# Ports.net
KiCad netlist of a schematic drawn in Altium Designer
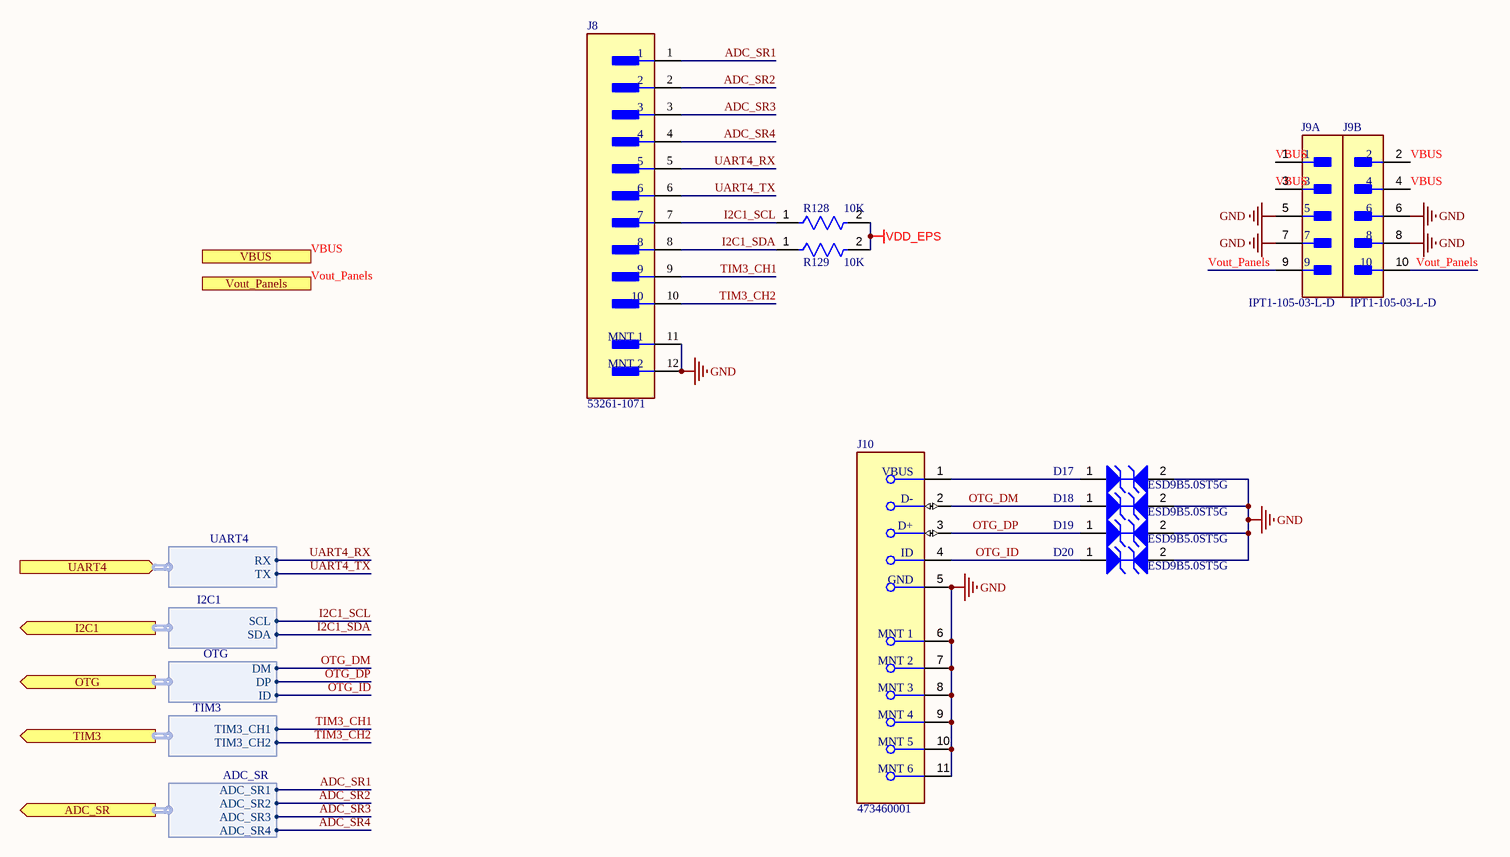
[diagram p0: Ports.SchDoc]

(export (version "E")
  (design (tool "Eeschema 10.0.6"))
  (components
    (comp (ref "D17")
      (value "ESD9B5.0ST5G")
      (footprint "ONSC-SOD-923-2-514AB-01_V")
      (fields (field (name "MANUFACTURER") "On Semiconductor"))
      (libsource (lib "Altium Content Vault") (part "ONSC-A1A2-2"))
    )
    (comp (ref "D18")
      (value "ESD9B5.0ST5G")
      (footprint "ONSC-SOD-923-2-514AB-01_V")
      (fields (field (name "MANUFACTURER") "On Semiconductor"))
      (libsource (lib "Altium Content Vault") (part "ONSC-A1A2-2"))
    )
    (comp (ref "D19")
      (value "ESD9B5.0ST5G")
      (footprint "ONSC-SOD-923-2-514AB-01_V")
      (fields (field (name "MANUFACTURER") "On Semiconductor"))
      (libsource (lib "Altium Content Vault") (part "ONSC-A1A2-2"))
    )
    (comp (ref "D20")
      (value "ESD9B5.0ST5G")
      (footprint "ONSC-SOD-923-2-514AB-01_V")
      (fields (field (name "MANUFACTURER") "On Semiconductor"))
      (libsource (lib "Altium Content Vault") (part "ONSC-A1A2-2"))
    )
    (comp (ref "J8")
      (value "53261-1071")
      (footprint "FP-532611071-MFG")
      (libsource (lib "Altium Content Vault") (part "6fa52caac0d1ee56d9e6a1d806c5b84"))
    )
    (comp (ref "J9")
      (value "IPT1-105-03-L-D")
      (footprint "FP-IPT1-105-03-L-D-MFG")
      (description "CONN HEADER VERT 10POS 2.54MM")
      (fields
        (field (name "MANUFACTURER") "Samtec")
        (field (name "OCTOPART") "https://octopart.com/ipt1-105-03-l-d-samtec-19544968")
      )
      (libsource (lib "") (part "544f42128f4185dcb88ce1ce9bf1982_1"))
    )
    (comp (ref "J10")
      (value "473460001")
      (footprint "FP-473460001-MFG")
      (description "CONN RCPT USB2.0 MICRO B SMD R/A")
      (fields
        (field (name "OCTOPART") "https://octopart.com/47346-0001-molex-7164928")
        (field (name "MANUFACTURER") "Molex")
      )
      (libsource (lib "Altium Content Vault") (part "53ae1f1d9b557310b43ca686e5bb76a"))
    )
    (comp (ref "R128")
      (value "10K")
      (footprint "FP-RK73B1J-MFG")
      (description "RES 10K OHM 5% 1/10W 0603")
      (fields (field (name "TOLERANCE") "5%"))
      (libsource (lib "Altium Content Vault") (part "1029c3af85768c4190bb7ad29bc67b5"))
    )
    (comp (ref "R129")
      (value "10K")
      (footprint "FP-RK73B1J-MFG")
      (description "RES 10K OHM 5% 1/10W 0603")
      (fields (field (name "TOLERANCE") "5%"))
      (libsource (lib "Altium Content Vault") (part "1029c3af85768c4190bb7ad29bc67b5"))
    )
  )
  (nets
    (net (code "6") (name "/ADC_SR1") (class "Default")
      (node (ref "J8") (pin "1") (pinfunction "1_1") (pintype "passive"))
    )
    (net (code "7") (name "/ADC_SR2") (class "Default")
      (node (ref "J8") (pin "2") (pinfunction "2_2") (pintype "passive"))
    )
    (net (code "8") (name "/ADC_SR3") (class "Default")
      (node (ref "J8") (pin "3") (pinfunction "3_3") (pintype "passive"))
    )
    (net (code "9") (name "/ADC_SR4") (class "Default")
      (node (ref "J8") (pin "4") (pinfunction "4_4") (pintype "passive"))
    )
    (net (code "10") (name "/I2C1_SCL") (class "Default")
      (node (ref "J8") (pin "7") (pinfunction "7_7") (pintype "passive"))
      (node (ref "R128") (pin "1") (pinfunction "1_1") (pintype "passive"))
    )
    (net (code "11") (name "/I2C1_SDA") (class "Default")
      (node (ref "J8") (pin "8") (pinfunction "8_8") (pintype "passive"))
      (node (ref "R129") (pin "1") (pinfunction "1_1") (pintype "passive"))
    )
    (net (code "12") (name "/OTG_DM") (class "Default")
      (node (ref "D18") (pin "1") (pinfunction "A1_1") (pintype "passive"))
      (node (ref "J10") (pin "2") (pinfunction "D-_2") (pintype "bidirectional"))
    )
    (net (code "13") (name "/OTG_DP") (class "Default")
      (node (ref "D19") (pin "1") (pinfunction "A1_1") (pintype "passive"))
      (node (ref "J10") (pin "3") (pinfunction "D+_3") (pintype "bidirectional"))
    )
    (net (code "14") (name "/OTG_ID") (class "Default")
      (node (ref "D20") (pin "1") (pinfunction "A1_1") (pintype "passive"))
      (node (ref "J10") (pin "4") (pinfunction "ID_4") (pintype "passive"))
    )
    (net (code "15") (name "/TIM3_CH1") (class "Default")
      (node (ref "J8") (pin "9") (pinfunction "9_9") (pintype "passive"))
    )
    (net (code "16") (name "/TIM3_CH2") (class "Default")
      (node (ref "J8") (pin "10") (pinfunction "10_10") (pintype "passive"))
    )
    (net (code "17") (name "/UART4_RX") (class "Default")
      (node (ref "J8") (pin "5") (pinfunction "5_5") (pintype "passive"))
    )
    (net (code "18") (name "/UART4_TX") (class "Default")
      (node (ref "J8") (pin "6") (pinfunction "6_6") (pintype "passive"))
    )
    (net (code "19") (name "/VBUS") (class "Default")
      (node (ref "J9") (pin "1") (pinfunction "1_1") (pintype "passive"))
      (node (ref "J9") (pin "2") (pinfunction "2_2") (pintype "passive"))
      (node (ref "J9") (pin "3") (pinfunction "3_3") (pintype "passive"))
      (node (ref "J9") (pin "4") (pinfunction "4_4") (pintype "passive"))
    )
    (net (code "20") (name "/Vout_Panels") (class "Default")
      (node (ref "J9") (pin "10") (pinfunction "10_10") (pintype "passive"))
      (node (ref "J9") (pin "9") (pinfunction "9_9") (pintype "passive"))
    )
    (net (code "26") (name "GND") (class "Default")
      (node (ref "D17") (pin "2") (pinfunction "A2_2") (pintype "passive"))
      (node (ref "D18") (pin "2") (pinfunction "A2_2") (pintype "passive"))
      (node (ref "D19") (pin "2") (pinfunction "A2_2") (pintype "passive"))
      (node (ref "D20") (pin "2") (pinfunction "A2_2") (pintype "passive"))
      (node (ref "J10") (pin "10") (pinfunction "MNT_5_10") (pintype "passive"))
      (node (ref "J10") (pin "11") (pinfunction "MNT_6_11") (pintype "passive"))
      (node (ref "J10") (pin "5") (pinfunction "GND_5") (pintype "power_in"))
      (node (ref "J10") (pin "6") (pinfunction "MNT_1_6") (pintype "passive"))
      (node (ref "J10") (pin "7") (pinfunction "MNT_2_7") (pintype "passive"))
      (node (ref "J10") (pin "8") (pinfunction "MNT_3_8") (pintype "passive"))
      (node (ref "J10") (pin "9") (pinfunction "MNT_4_9") (pintype "passive"))
      (node (ref "J8") (pin "11") (pinfunction "MNT_1_11") (pintype "passive"))
      (node (ref "J8") (pin "12") (pinfunction "MNT_2_12") (pintype "passive"))
      (node (ref "J9") (pin "5") (pinfunction "5_5") (pintype "passive"))
      (node (ref "J9") (pin "6") (pinfunction "6_6") (pintype "passive"))
      (node (ref "J9") (pin "7") (pinfunction "7_7") (pintype "passive"))
      (node (ref "J9") (pin "8") (pinfunction "8_8") (pintype "passive"))
    )
    (net (code "27") (name "Net-(D17-A1)") (class "Default")
      (node (ref "D17") (pin "1") (pinfunction "A1_1") (pintype "passive"))
      (node (ref "J10") (pin "1") (pinfunction "VBUS_1") (pintype "power_in"))
    )
    (net (code "28") (name "VDD_EPS") (class "Default")
      (node (ref "R128") (pin "2") (pinfunction "2_2") (pintype "passive"))
      (node (ref "R129") (pin "2") (pinfunction "2_2") (pintype "passive"))
    )
  )
)
